# RJ45_2.net
KiCad netlist of a schematic drawn in Altium Designer
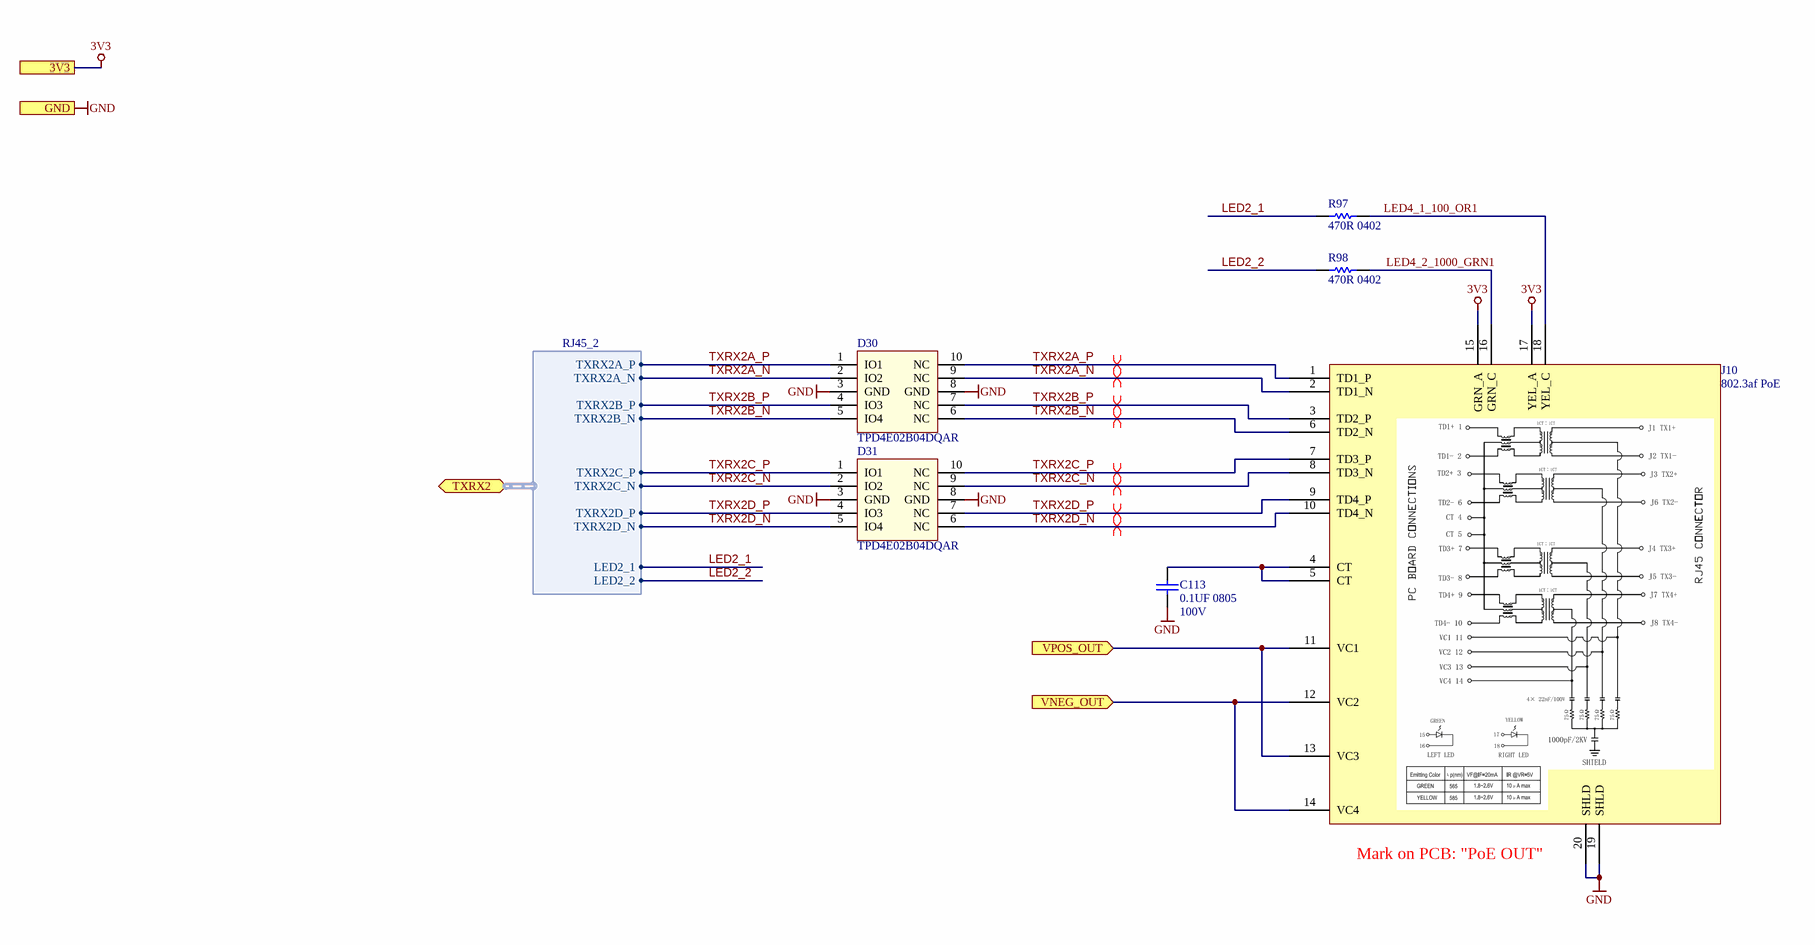
[diagram p0: RJ45_2.SchDoc]

(export (version "E")
  (design (tool "Eeschema 10.0.6"))
  (components
    (comp (ref "C113")
      (value "0.1UF 0805")
      (footprint "CAPC0805(2012)145_N")
      (description "CAP CER 0.1UF 100V X7R 0805")
      (fields (field (name "TOLERANCE") "10%") (field (name "VOLTAGE RATING") "100V"))
      (libsource (lib "PCBProject") (part "CL21B104KCFNNNE"))
    )
    (comp (ref "D30")
      (value "TPD4E02B04DQAR")
      (footprint "TPD4E02B04DQAR")
      (libsource (lib "LuxonisMaster") (part "TPD4E02B04DQAR"))
    )
    (comp (ref "D31")
      (value "TPD4E02B04DQAR")
      (footprint "TPD4E02B04DQAR")
      (libsource (lib "LuxonisMaster") (part "TPD4E02B04DQAR"))
    )
    (comp (ref "J10")
      (value "802.3af PoE")
      (footprint "BW2098POE:TRJG0926HENL")
      (description "CONN MAGJACK 1PORT 1000 BASET")
      (libsource (lib "BW2098POE") (part "TRJG0926HENL"))
    )
    (comp (ref "R97")
      (value "470R 0402")
      (footprint "RESC0402(1005)_N")
      (description "RES SMD 470 OHM 1% 1/16W 0402")
      (fields (field (name "TOLERANCE") "1%"))
      (libsource (lib "LuxonisMaster") (part "CRCW0402470RFKED"))
    )
    (comp (ref "R98")
      (value "470R 0402")
      (footprint "RESC0402(1005)_N")
      (description "RES SMD 470 OHM 1% 1/16W 0402")
      (fields (field (name "TOLERANCE") "1%"))
      (libsource (lib "LuxonisMaster") (part "CRCW0402470RFKED"))
    )
  )
  (nets
    (net (code "2") (name "/LED2_1") (class "Default")
      (node (ref "R97") (pin "1") (pinfunction "1_1") (pintype "passive"))
    )
    (net (code "3") (name "/LED2_2") (class "Default")
      (node (ref "R98") (pin "1") (pinfunction "1_1") (pintype "passive"))
    )
    (net (code "4") (name "/LED4_1_100_OR1") (class "Default")
      (node (ref "J10") (pin "18") (pinfunction "YEL_C_18") (pintype "passive"))
      (node (ref "R97") (pin "2") (pinfunction "2_2") (pintype "passive"))
    )
    (net (code "5") (name "/LED4_2_1000_GRN1") (class "Default")
      (node (ref "J10") (pin "16") (pinfunction "GRN_C_16") (pintype "passive"))
      (node (ref "R98") (pin "2") (pinfunction "2_2") (pintype "passive"))
    )
    (net (code "6") (name "/TXRX2A_N") (class "Default")
      (node (ref "D30") (pin "2") (pinfunction "IO2_2") (pintype "passive"))
      (node (ref "D30") (pin "9") (pinfunction "NC_9") (pintype "passive"))
      (node (ref "J10") (pin "2") (pinfunction "TD1_N_2") (pintype "passive"))
    )
    (net (code "7") (name "/TXRX2A_P") (class "Default")
      (node (ref "D30") (pin "1") (pinfunction "IO1_1") (pintype "passive"))
      (node (ref "D30") (pin "10") (pinfunction "NC_10") (pintype "passive"))
      (node (ref "J10") (pin "1") (pinfunction "TD1_P_1") (pintype "passive"))
    )
    (net (code "8") (name "/TXRX2B_N") (class "Default")
      (node (ref "D30") (pin "5") (pinfunction "IO4_5") (pintype "passive"))
      (node (ref "D30") (pin "6") (pinfunction "NC_6") (pintype "passive"))
      (node (ref "J10") (pin "6") (pinfunction "TD2_N_6") (pintype "passive"))
    )
    (net (code "9") (name "/TXRX2B_P") (class "Default")
      (node (ref "D30") (pin "4") (pinfunction "IO3_4") (pintype "passive"))
      (node (ref "D30") (pin "7") (pinfunction "NC_7") (pintype "passive"))
      (node (ref "J10") (pin "3") (pinfunction "TD2_P_3") (pintype "passive"))
    )
    (net (code "10") (name "/TXRX2C_N") (class "Default")
      (node (ref "D31") (pin "2") (pinfunction "IO2_2") (pintype "passive"))
      (node (ref "D31") (pin "9") (pinfunction "NC_9") (pintype "passive"))
      (node (ref "J10") (pin "8") (pinfunction "TD3_N_8") (pintype "passive"))
    )
    (net (code "11") (name "/TXRX2C_P") (class "Default")
      (node (ref "D31") (pin "1") (pinfunction "IO1_1") (pintype "passive"))
      (node (ref "D31") (pin "10") (pinfunction "NC_10") (pintype "passive"))
      (node (ref "J10") (pin "7") (pinfunction "TD3_P_7") (pintype "passive"))
    )
    (net (code "12") (name "/TXRX2D_N") (class "Default")
      (node (ref "D31") (pin "5") (pinfunction "IO4_5") (pintype "passive"))
      (node (ref "D31") (pin "6") (pinfunction "NC_6") (pintype "passive"))
      (node (ref "J10") (pin "10") (pinfunction "TD4_N_10") (pintype "passive"))
    )
    (net (code "13") (name "/TXRX2D_P") (class "Default")
      (node (ref "D31") (pin "4") (pinfunction "IO3_4") (pintype "passive"))
      (node (ref "D31") (pin "7") (pinfunction "NC_7") (pintype "passive"))
      (node (ref "J10") (pin "9") (pinfunction "TD4_P_9") (pintype "passive"))
    )
    (net (code "14") (name "/VNEG_OUT") (class "Default")
      (node (ref "J10") (pin "12") (pinfunction "VC2_12") (pintype "passive"))
      (node (ref "J10") (pin "14") (pinfunction "VC4_14") (pintype "passive"))
    )
    (net (code "15") (name "/VPOS_OUT") (class "Default")
      (node (ref "J10") (pin "11") (pinfunction "VC1_11") (pintype "passive"))
      (node (ref "J10") (pin "13") (pinfunction "VC3_13") (pintype "passive"))
    )
    (net (code "17") (name "3V3") (class "Default")
      (node (ref "J10") (pin "15") (pinfunction "GRN_A_15") (pintype "passive"))
      (node (ref "J10") (pin "17") (pinfunction "YEL_A_17") (pintype "passive"))
    )
    (net (code "18") (name "GND") (class "Default")
      (node (ref "C113") (pin "1") (pinfunction "1_1") (pintype "passive"))
      (node (ref "D30") (pin "3") (pinfunction "GND_3") (pintype "passive"))
      (node (ref "D30") (pin "8") (pinfunction "GND_8") (pintype "passive"))
      (node (ref "D31") (pin "3") (pinfunction "GND_3") (pintype "passive"))
      (node (ref "D31") (pin "8") (pinfunction "GND_8") (pintype "passive"))
      (node (ref "J10") (pin "19") (pinfunction "SHLD_19") (pintype "passive"))
      (node (ref "J10") (pin "20") (pinfunction "SHLD_20") (pintype "passive"))
    )
    (net (code "19") (name "Net-(C113-Pad2)") (class "Default")
      (node (ref "C113") (pin "2") (pinfunction "2_2") (pintype "passive"))
      (node (ref "J10") (pin "4") (pinfunction "CT_4") (pintype "passive"))
      (node (ref "J10") (pin "5") (pinfunction "CT_5") (pintype "passive"))
    )
  )
)
